# motor_connector.net
KiCad netlist of a schematic drawn in Altium Designer
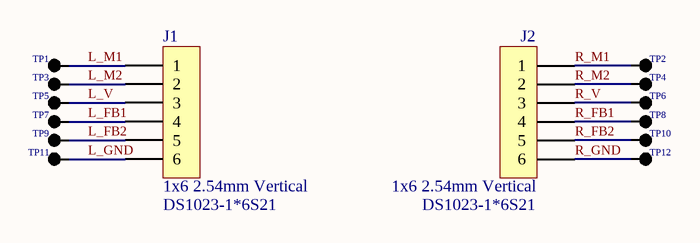
[diagram p0: motor_connector.SchDoc]

(export (version "E")
  (design (tool "Eeschema 10.0.6"))
  (components
    (comp (ref "J1")
      (value "DS1023-1*6S21")
      (footprint "J_HEADER_1x6_2.54_VERTICAL")
      (description "Pin Header")
      (fields
        (field (name "SCH_FOOTPRINT") "1x6 2.54mm Vertical")
        (field (name "PART NUMBER") "J_HEADER_1x6_2.54_VERTICAL")
        (field (name "MANUFACTURER") "Connfly")
      )
      (libsource (lib "Library") (part "J_HEADER_1x6"))
    )
    (comp (ref "J2")
      (value "DS1023-1*6S21")
      (footprint "J_HEADER_1x6_2.54_VERTICAL")
      (description "Pin Header")
      (fields
        (field (name "SCH_FOOTPRINT") "1x6 2.54mm Vertical")
        (field (name "PART NUMBER") "J_HEADER_1x6_2.54_VERTICAL")
        (field (name "MANUFACTURER") "Connfly")
      )
      (libsource (lib "") (part "J_HEADER_1x6_1"))
    )
    (comp (ref "TP1")
      (value "Single pin")
      (footprint "TP_1PIN")
      (description "Testpoint")
      (fields (field (name "PART NUMBER") "TP_1PIN"))
      (libsource (lib "Library") (part "TP_TESTPOINT"))
    )
    (comp (ref "TP2")
      (value "Single pin")
      (footprint "TP_1PIN")
      (description "Testpoint")
      (fields (field (name "PART NUMBER") "TP_1PIN"))
      (libsource (lib "Library") (part "TP_TESTPOINT"))
    )
    (comp (ref "TP3")
      (value "Single pin")
      (footprint "TP_1PIN")
      (description "Testpoint")
      (fields (field (name "PART NUMBER") "TP_1PIN"))
      (libsource (lib "Library") (part "TP_TESTPOINT"))
    )
    (comp (ref "TP4")
      (value "Single pin")
      (footprint "TP_1PIN")
      (description "Testpoint")
      (fields (field (name "PART NUMBER") "TP_1PIN"))
      (libsource (lib "Library") (part "TP_TESTPOINT"))
    )
    (comp (ref "TP5")
      (value "Single pin")
      (footprint "TP_1PIN")
      (description "Testpoint")
      (fields (field (name "PART NUMBER") "TP_1PIN"))
      (libsource (lib "Library") (part "TP_TESTPOINT"))
    )
    (comp (ref "TP6")
      (value "Single pin")
      (footprint "TP_1PIN")
      (description "Testpoint")
      (fields (field (name "PART NUMBER") "TP_1PIN"))
      (libsource (lib "Library") (part "TP_TESTPOINT"))
    )
    (comp (ref "TP7")
      (value "Single pin")
      (footprint "TP_1PIN")
      (description "Testpoint")
      (fields (field (name "PART NUMBER") "TP_1PIN"))
      (libsource (lib "Library") (part "TP_TESTPOINT"))
    )
    (comp (ref "TP8")
      (value "Single pin")
      (footprint "TP_1PIN")
      (description "Testpoint")
      (fields (field (name "PART NUMBER") "TP_1PIN"))
      (libsource (lib "Library") (part "TP_TESTPOINT"))
    )
    (comp (ref "TP9")
      (value "Single pin")
      (footprint "TP_1PIN")
      (description "Testpoint")
      (fields (field (name "PART NUMBER") "TP_1PIN"))
      (libsource (lib "Library") (part "TP_TESTPOINT"))
    )
    (comp (ref "TP10")
      (value "Single pin")
      (footprint "TP_1PIN")
      (description "Testpoint")
      (fields (field (name "PART NUMBER") "TP_1PIN"))
      (libsource (lib "Library") (part "TP_TESTPOINT"))
    )
    (comp (ref "TP11")
      (value "Single pin")
      (footprint "TP_1PIN")
      (description "Testpoint")
      (fields (field (name "PART NUMBER") "TP_1PIN"))
      (libsource (lib "Library") (part "TP_TESTPOINT"))
    )
    (comp (ref "TP12")
      (value "Single pin")
      (footprint "TP_1PIN")
      (description "Testpoint")
      (fields (field (name "PART NUMBER") "TP_1PIN"))
      (libsource (lib "Library") (part "TP_TESTPOINT"))
    )
  )
  (nets
    (net (code "1") (name "/L_FB1") (class "Default")
      (node (ref "J1") (pin "4") (pinfunction "4_4") (pintype "passive"))
      (node (ref "TP7") (pin "1") (pinfunction "TP_1") (pintype "passive"))
    )
    (net (code "2") (name "/L_FB2") (class "Default")
      (node (ref "J1") (pin "5") (pinfunction "5_5") (pintype "passive"))
      (node (ref "TP9") (pin "1") (pinfunction "TP_1") (pintype "passive"))
    )
    (net (code "3") (name "/L_GND") (class "Default")
      (node (ref "J1") (pin "6") (pinfunction "6_6") (pintype "passive"))
      (node (ref "TP11") (pin "1") (pinfunction "TP_1") (pintype "passive"))
    )
    (net (code "4") (name "/L_M1") (class "Default")
      (node (ref "J1") (pin "1") (pinfunction "1_1") (pintype "passive"))
      (node (ref "TP1") (pin "1") (pinfunction "TP_1") (pintype "passive"))
    )
    (net (code "5") (name "/L_M2") (class "Default")
      (node (ref "J1") (pin "2") (pinfunction "2_2") (pintype "passive"))
      (node (ref "TP3") (pin "1") (pinfunction "TP_1") (pintype "passive"))
    )
    (net (code "6") (name "/L_V") (class "Default")
      (node (ref "J1") (pin "3") (pinfunction "3_3") (pintype "passive"))
      (node (ref "TP5") (pin "1") (pinfunction "TP_1") (pintype "passive"))
    )
    (net (code "7") (name "/R_FB1") (class "Default")
      (node (ref "J2") (pin "4") (pinfunction "4_4") (pintype "passive"))
      (node (ref "TP8") (pin "1") (pinfunction "TP_1") (pintype "passive"))
    )
    (net (code "8") (name "/R_FB2") (class "Default")
      (node (ref "J2") (pin "5") (pinfunction "5_5") (pintype "passive"))
      (node (ref "TP10") (pin "1") (pinfunction "TP_1") (pintype "passive"))
    )
    (net (code "9") (name "/R_GND") (class "Default")
      (node (ref "J2") (pin "6") (pinfunction "6_6") (pintype "passive"))
      (node (ref "TP12") (pin "1") (pinfunction "TP_1") (pintype "passive"))
    )
    (net (code "10") (name "/R_M1") (class "Default")
      (node (ref "J2") (pin "1") (pinfunction "1_1") (pintype "passive"))
      (node (ref "TP2") (pin "1") (pinfunction "TP_1") (pintype "passive"))
    )
    (net (code "11") (name "/R_M2") (class "Default")
      (node (ref "J2") (pin "2") (pinfunction "2_2") (pintype "passive"))
      (node (ref "TP4") (pin "1") (pinfunction "TP_1") (pintype "passive"))
    )
    (net (code "12") (name "/R_V") (class "Default")
      (node (ref "J2") (pin "3") (pinfunction "3_3") (pintype "passive"))
      (node (ref "TP6") (pin "1") (pinfunction "TP_1") (pintype "passive"))
    )
  )
)
